# nrf24L01Shield.net
KiCad netlist of a schematic drawn in EAGLE
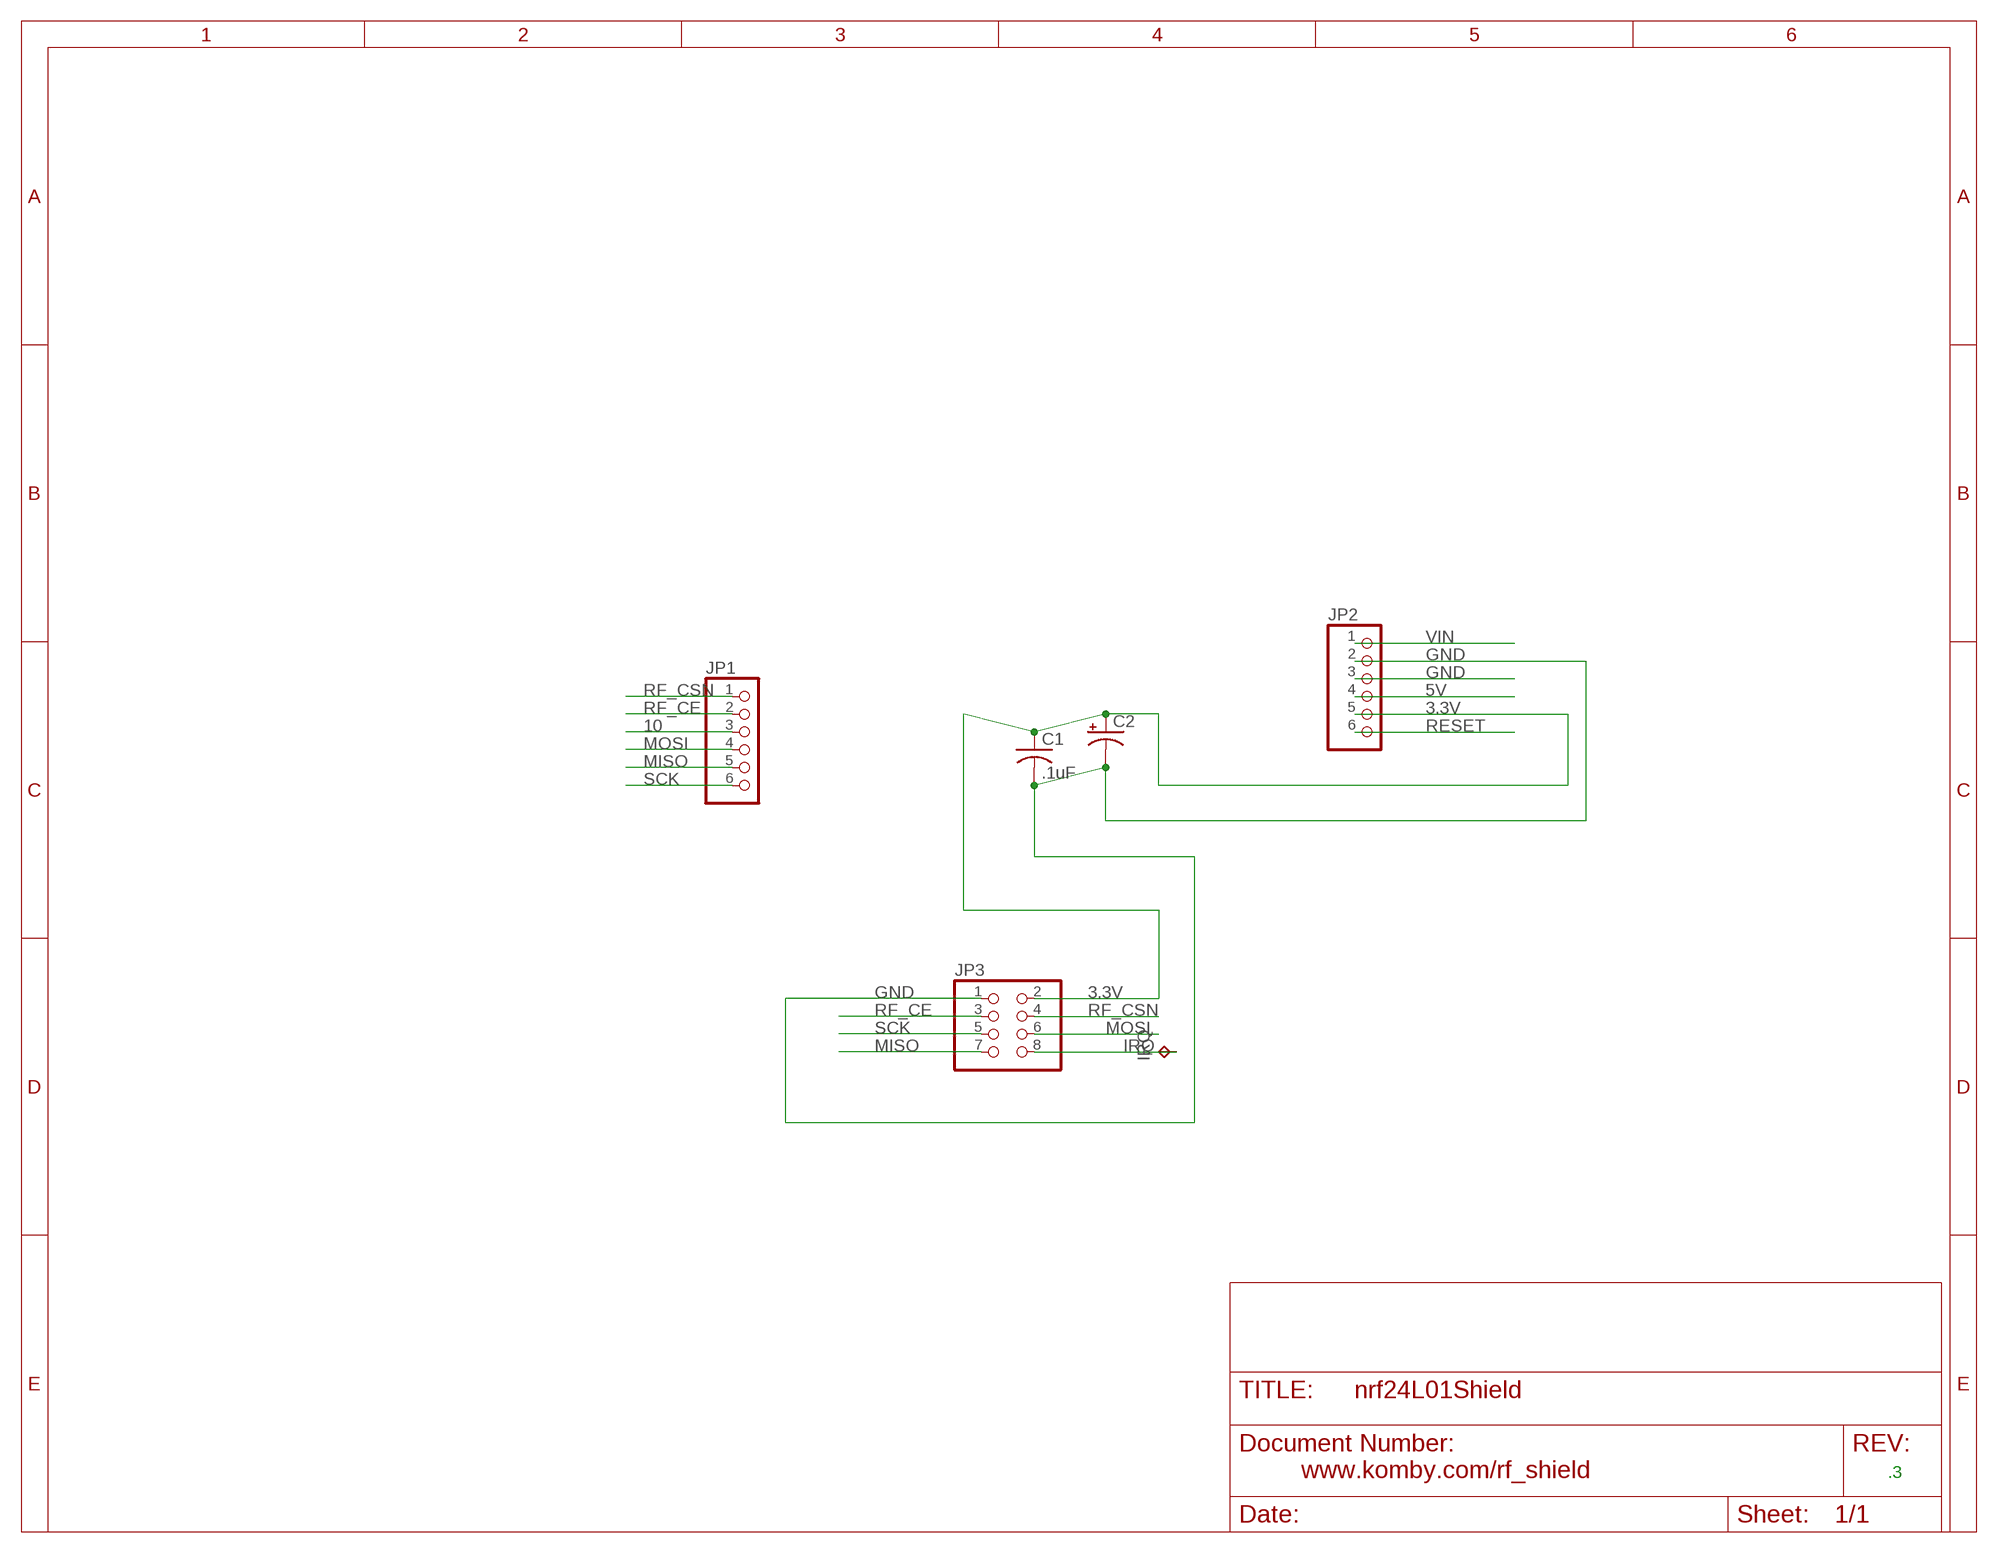
[diagram p0: schematic, sheet 1]

(export (version "E")
  (design (tool "Eeschema 10.0.6"))
  (components
    (comp (ref "C1")
      (value ".1uF")
      (footprint "eagle-import:C025-024X044")
      (libsource (lib "eagle-import") (part "C-US025-024X044"))
    )
    (comp (ref "C2")
      (value "CPOL-USE2.5-6")
      (footprint "eagle-import:E2,5-6")
      (libsource (lib "eagle-import") (part "CPOL-USE2.5-6"))
    )
    (comp (ref "IRQ")
      (value "IRQ")
      (footprint "eagle-import:P1-13")
      (libsource (lib "eagle-import") (part "TPPAD1-13"))
    )
    (comp (ref "JP1")
      (value "PINHD-1X6B")
      (footprint "eagle-import:1X06-BIG")
      (libsource (lib "eagle-import") (part "PINHD-1X6B"))
    )
    (comp (ref "JP2")
      (value "PINHD-1X6B")
      (footprint "eagle-import:1X06-BIG")
      (libsource (lib "eagle-import") (part "PINHD-1X6B"))
    )
    (comp (ref "JP3")
      (value "PINHD-2X4")
      (footprint "eagle-import:2X04")
      (libsource (lib "eagle-import") (part "PINHD-2X4"))
    )
  )
  (nets
    (net (code "1") (name "/3.3V") (class "Default")
      (node (ref "C1") (pin "1") (pinfunction "1_1") (pintype "passive"))
      (node (ref "C2") (pin "+") (pinfunction "+_+") (pintype "passive"))
      (node (ref "JP2") (pin "5") (pinfunction "5_5") (pintype "passive"))
      (node (ref "JP3") (pin "2") (pinfunction "2_2") (pintype "passive"))
    )
    (net (code "2") (name "/5V") (class "Default")
      (node (ref "JP2") (pin "4") (pinfunction "4_4") (pintype "passive"))
    )
    (net (code "3") (name "/10") (class "Default")
      (node (ref "JP1") (pin "3") (pinfunction "3_3") (pintype "passive"))
    )
    (net (code "4") (name "/GND") (class "Default")
      (node (ref "C1") (pin "2") (pinfunction "2_2") (pintype "passive"))
      (node (ref "C2") (pin "-") (pinfunction "-_-") (pintype "passive"))
      (node (ref "JP2") (pin "2") (pinfunction "2_2") (pintype "passive"))
      (node (ref "JP2") (pin "3") (pinfunction "3_3") (pintype "passive"))
      (node (ref "JP3") (pin "1") (pinfunction "1_1") (pintype "passive"))
    )
    (net (code "5") (name "/IRQ") (class "Default")
      (node (ref "IRQ") (pin "TP") (pinfunction "TP_TP") (pintype "input"))
      (node (ref "JP3") (pin "8") (pinfunction "8_8") (pintype "passive"))
    )
    (net (code "6") (name "/MISO") (class "Default")
      (node (ref "JP1") (pin "5") (pinfunction "5_5") (pintype "passive"))
      (node (ref "JP3") (pin "7") (pinfunction "7_7") (pintype "passive"))
    )
    (net (code "7") (name "/MOSI") (class "Default")
      (node (ref "JP1") (pin "4") (pinfunction "4_4") (pintype "passive"))
      (node (ref "JP3") (pin "6") (pinfunction "6_6") (pintype "passive"))
    )
    (net (code "8") (name "/RESET") (class "Default")
      (node (ref "JP2") (pin "6") (pinfunction "6_6") (pintype "passive"))
    )
    (net (code "9") (name "/RF_CE") (class "Default")
      (node (ref "JP1") (pin "2") (pinfunction "2_2") (pintype "passive"))
      (node (ref "JP3") (pin "3") (pinfunction "3_3") (pintype "passive"))
    )
    (net (code "10") (name "/RF_CSN") (class "Default")
      (node (ref "JP1") (pin "1") (pinfunction "1_1") (pintype "passive"))
      (node (ref "JP3") (pin "4") (pinfunction "4_4") (pintype "passive"))
    )
    (net (code "11") (name "/SCK") (class "Default")
      (node (ref "JP1") (pin "6") (pinfunction "6_6") (pintype "passive"))
      (node (ref "JP3") (pin "5") (pinfunction "5_5") (pintype "passive"))
    )
    (net (code "12") (name "/VIN") (class "Default")
      (node (ref "JP2") (pin "1") (pinfunction "1_1") (pintype "passive"))
    )
  )
)
